# SCH_praktikum-gib-mir-mal-ne-wago.net
KiCad netlist of a schematic drawn in EasyEDA
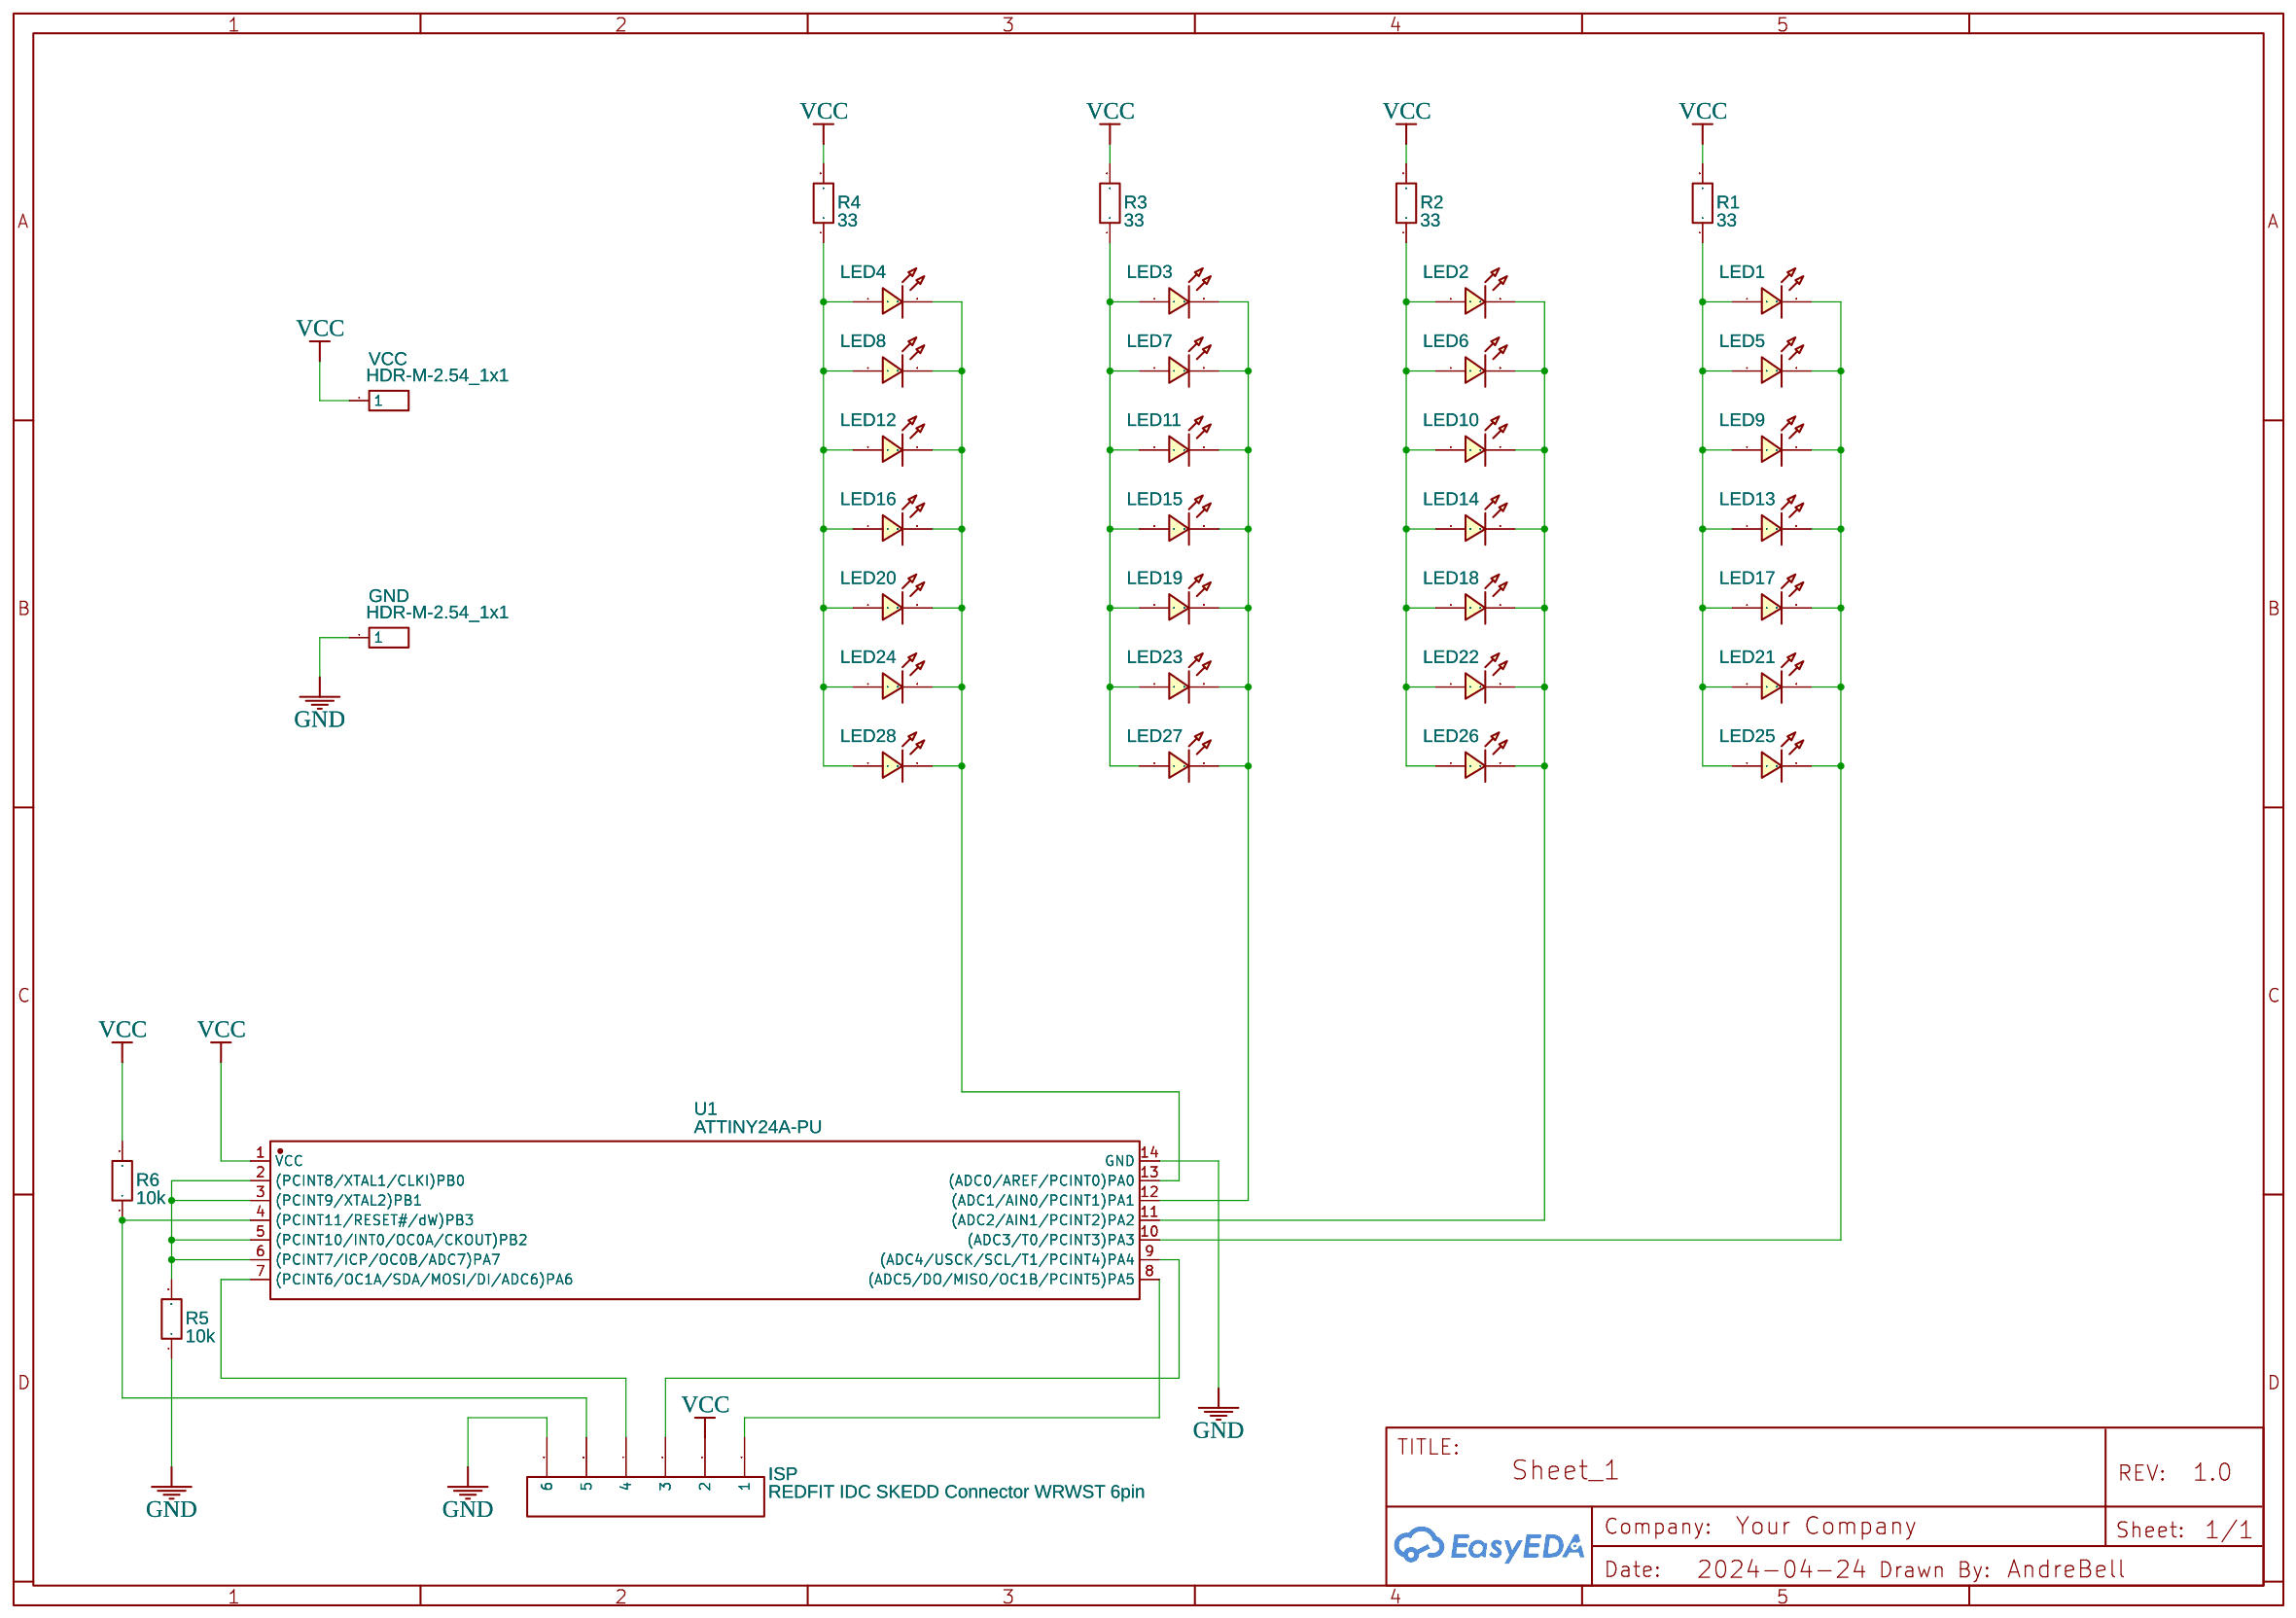
[diagram p0: schematic sheet]

(export (version "E")
  (design (tool "Eeschema 10.0.6"))
  (components
    (comp (ref "GND") (value "HDR-M-2.54_1x1") (libsource (lib "") (part "HDR-M-2.54_1x1")))
    (comp (ref "ISP")
      (value "REDFIT IDC SKEDD Connector WRWST 6pin")
      (libsource (lib "") (part "REDFIT IDC SKEDD Connector WRWST 6pin"))
    )
    (comp (ref "LED1")
      (value "LED-TH-3mm_G")
      (fields
        (field (name "Manufacturer Part") "204-10SYGD/S530-E3")
        (field (name "Manufacturer") "EVERLIGHT(台湾亿光)")
      )
      (libsource (lib "") (part "LED-TH-3mm_G"))
    )
    (comp (ref "LED2")
      (value "LED-TH-3mm_G")
      (fields
        (field (name "Manufacturer Part") "204-10SYGD/S530-E3")
        (field (name "Manufacturer") "EVERLIGHT(台湾亿光)")
      )
      (libsource (lib "") (part "LED-TH-3mm_G"))
    )
    (comp (ref "LED3")
      (value "LED-TH-3mm_G")
      (fields
        (field (name "Manufacturer Part") "204-10SYGD/S530-E3")
        (field (name "Manufacturer") "EVERLIGHT(台湾亿光)")
      )
      (libsource (lib "") (part "LED-TH-3mm_G"))
    )
    (comp (ref "LED4")
      (value "LED-TH-3mm_G")
      (fields
        (field (name "Manufacturer Part") "204-10SYGD/S530-E3")
        (field (name "Manufacturer") "EVERLIGHT(台湾亿光)")
      )
      (libsource (lib "") (part "LED-TH-3mm_G"))
    )
    (comp (ref "LED5")
      (value "LED-TH-3mm_G")
      (fields
        (field (name "Manufacturer Part") "204-10SYGD/S530-E3")
        (field (name "Manufacturer") "EVERLIGHT(台湾亿光)")
      )
      (libsource (lib "") (part "LED-TH-3mm_G"))
    )
    (comp (ref "LED6")
      (value "LED-TH-3mm_G")
      (fields
        (field (name "Manufacturer Part") "204-10SYGD/S530-E3")
        (field (name "Manufacturer") "EVERLIGHT(台湾亿光)")
      )
      (libsource (lib "") (part "LED-TH-3mm_G"))
    )
    (comp (ref "LED7")
      (value "LED-TH-3mm_G")
      (fields
        (field (name "Manufacturer Part") "204-10SYGD/S530-E3")
        (field (name "Manufacturer") "EVERLIGHT(台湾亿光)")
      )
      (libsource (lib "") (part "LED-TH-3mm_G"))
    )
    (comp (ref "LED8")
      (value "LED-TH-3mm_G")
      (fields
        (field (name "Manufacturer Part") "204-10SYGD/S530-E3")
        (field (name "Manufacturer") "EVERLIGHT(台湾亿光)")
      )
      (libsource (lib "") (part "LED-TH-3mm_G"))
    )
    (comp (ref "LED9")
      (value "LED-TH-3mm_G")
      (fields
        (field (name "Manufacturer Part") "204-10SYGD/S530-E3")
        (field (name "Manufacturer") "EVERLIGHT(台湾亿光)")
      )
      (libsource (lib "") (part "LED-TH-3mm_G"))
    )
    (comp (ref "LED10")
      (value "LED-TH-3mm_G")
      (fields
        (field (name "Manufacturer Part") "204-10SYGD/S530-E3")
        (field (name "Manufacturer") "EVERLIGHT(台湾亿光)")
      )
      (libsource (lib "") (part "LED-TH-3mm_G"))
    )
    (comp (ref "LED11")
      (value "LED-TH-3mm_G")
      (fields
        (field (name "Manufacturer Part") "204-10SYGD/S530-E3")
        (field (name "Manufacturer") "EVERLIGHT(台湾亿光)")
      )
      (libsource (lib "") (part "LED-TH-3mm_G"))
    )
    (comp (ref "LED12")
      (value "LED-TH-3mm_G")
      (fields
        (field (name "Manufacturer Part") "204-10SYGD/S530-E3")
        (field (name "Manufacturer") "EVERLIGHT(台湾亿光)")
      )
      (libsource (lib "") (part "LED-TH-3mm_G"))
    )
    (comp (ref "LED13")
      (value "LED-TH-3mm_G")
      (fields
        (field (name "Manufacturer Part") "204-10SYGD/S530-E3")
        (field (name "Manufacturer") "EVERLIGHT(台湾亿光)")
      )
      (libsource (lib "") (part "LED-TH-3mm_G"))
    )
    (comp (ref "LED14")
      (value "LED-TH-3mm_G")
      (fields
        (field (name "Manufacturer Part") "204-10SYGD/S530-E3")
        (field (name "Manufacturer") "EVERLIGHT(台湾亿光)")
      )
      (libsource (lib "") (part "LED-TH-3mm_G"))
    )
    (comp (ref "LED15")
      (value "LED-TH-3mm_G")
      (fields
        (field (name "Manufacturer Part") "204-10SYGD/S530-E3")
        (field (name "Manufacturer") "EVERLIGHT(台湾亿光)")
      )
      (libsource (lib "") (part "LED-TH-3mm_G"))
    )
    (comp (ref "LED16")
      (value "LED-TH-3mm_G")
      (fields
        (field (name "Manufacturer Part") "204-10SYGD/S530-E3")
        (field (name "Manufacturer") "EVERLIGHT(台湾亿光)")
      )
      (libsource (lib "") (part "LED-TH-3mm_G"))
    )
    (comp (ref "LED17")
      (value "LED-TH-3mm_G")
      (fields
        (field (name "Manufacturer Part") "204-10SYGD/S530-E3")
        (field (name "Manufacturer") "EVERLIGHT(台湾亿光)")
      )
      (libsource (lib "") (part "LED-TH-3mm_G"))
    )
    (comp (ref "LED18")
      (value "LED-TH-3mm_G")
      (fields
        (field (name "Manufacturer Part") "204-10SYGD/S530-E3")
        (field (name "Manufacturer") "EVERLIGHT(台湾亿光)")
      )
      (libsource (lib "") (part "LED-TH-3mm_G"))
    )
    (comp (ref "LED19")
      (value "LED-TH-3mm_G")
      (fields
        (field (name "Manufacturer Part") "204-10SYGD/S530-E3")
        (field (name "Manufacturer") "EVERLIGHT(台湾亿光)")
      )
      (libsource (lib "") (part "LED-TH-3mm_G"))
    )
    (comp (ref "LED20")
      (value "LED-TH-3mm_G")
      (fields
        (field (name "Manufacturer Part") "204-10SYGD/S530-E3")
        (field (name "Manufacturer") "EVERLIGHT(台湾亿光)")
      )
      (libsource (lib "") (part "LED-TH-3mm_G"))
    )
    (comp (ref "LED21")
      (value "LED-TH-3mm_G")
      (fields
        (field (name "Manufacturer Part") "204-10SYGD/S530-E3")
        (field (name "Manufacturer") "EVERLIGHT(台湾亿光)")
      )
      (libsource (lib "") (part "LED-TH-3mm_G"))
    )
    (comp (ref "LED22")
      (value "LED-TH-3mm_G")
      (fields
        (field (name "Manufacturer Part") "204-10SYGD/S530-E3")
        (field (name "Manufacturer") "EVERLIGHT(台湾亿光)")
      )
      (libsource (lib "") (part "LED-TH-3mm_G"))
    )
    (comp (ref "LED23")
      (value "LED-TH-3mm_G")
      (fields
        (field (name "Manufacturer Part") "204-10SYGD/S530-E3")
        (field (name "Manufacturer") "EVERLIGHT(台湾亿光)")
      )
      (libsource (lib "") (part "LED-TH-3mm_G"))
    )
    (comp (ref "LED24")
      (value "LED-TH-3mm_G")
      (fields
        (field (name "Manufacturer Part") "204-10SYGD/S530-E3")
        (field (name "Manufacturer") "EVERLIGHT(台湾亿光)")
      )
      (libsource (lib "") (part "LED-TH-3mm_G"))
    )
    (comp (ref "LED25")
      (value "LED-TH-3mm_G")
      (fields
        (field (name "Manufacturer Part") "204-10SYGD/S530-E3")
        (field (name "Manufacturer") "EVERLIGHT(台湾亿光)")
      )
      (libsource (lib "") (part "LED-TH-3mm_G"))
    )
    (comp (ref "LED26")
      (value "LED-TH-3mm_G")
      (fields
        (field (name "Manufacturer Part") "204-10SYGD/S530-E3")
        (field (name "Manufacturer") "EVERLIGHT(台湾亿光)")
      )
      (libsource (lib "") (part "LED-TH-3mm_G"))
    )
    (comp (ref "LED27")
      (value "LED-TH-3mm_G")
      (fields
        (field (name "Manufacturer Part") "204-10SYGD/S530-E3")
        (field (name "Manufacturer") "EVERLIGHT(台湾亿光)")
      )
      (libsource (lib "") (part "LED-TH-3mm_G"))
    )
    (comp (ref "LED28")
      (value "LED-TH-3mm_G")
      (fields
        (field (name "Manufacturer Part") "204-10SYGD/S530-E3")
        (field (name "Manufacturer") "EVERLIGHT(台湾亿光)")
      )
      (libsource (lib "") (part "LED-TH-3mm_G"))
    )
    (comp (ref "R1") (value "33") (libsource (lib "") (part "R_AXIAL-0.3_EU")))
    (comp (ref "R2") (value "33") (libsource (lib "") (part "R_AXIAL-0.3_EU")))
    (comp (ref "R3") (value "33") (libsource (lib "") (part "R_AXIAL-0.3_EU")))
    (comp (ref "R4") (value "33") (libsource (lib "") (part "R_AXIAL-0.3_EU")))
    (comp (ref "R5") (value "10k") (libsource (lib "") (part "R_AXIAL-0.3_EU")))
    (comp (ref "R6") (value "10k") (libsource (lib "") (part "R_AXIAL-0.3_EU")))
    (comp (ref "U1")
      (value "ATTINY24A-PU")
      (fields (field (name "Manufacturer") "MICROCHIP(美国微芯)"))
      (libsource (lib "") (part "ATTINY24A-PU"))
    )
    (comp (ref "VCC") (value "HDR-M-2.54_1x1") (libsource (lib "") (part "HDR-M-2.54_1x1_1")))
  )
  (nets
    (net (code "1") (name "GND") (class "Default")
      (node (ref "GND") (pin "1") (pinfunction "1_1") (pintype "input"))
      (node (ref "ISP") (pin "6") (pinfunction "6_6") (pintype "unspecified"))
      (node (ref "R5") (pin "1") (pinfunction "1_1") (pintype "unspecified"))
      (node (ref "U1") (pin "14") (pinfunction "GND_14") (pintype "unspecified"))
    )
    (net (code "2") (name "Net-(LED1-Pad1)") (class "Default")
      (node (ref "LED1") (pin "1") (pinfunction "1_1") (pintype "unspecified"))
      (node (ref "LED13") (pin "1") (pinfunction "1_1") (pintype "unspecified"))
      (node (ref "LED17") (pin "1") (pinfunction "1_1") (pintype "unspecified"))
      (node (ref "LED21") (pin "1") (pinfunction "1_1") (pintype "unspecified"))
      (node (ref "LED25") (pin "1") (pinfunction "1_1") (pintype "unspecified"))
      (node (ref "LED5") (pin "1") (pinfunction "1_1") (pintype "unspecified"))
      (node (ref "LED9") (pin "1") (pinfunction "1_1") (pintype "unspecified"))
      (node (ref "R1") (pin "1") (pinfunction "1_1") (pintype "unspecified"))
    )
    (net (code "3") (name "Net-(LED10-Pad1)") (class "Default")
      (node (ref "LED10") (pin "1") (pinfunction "1_1") (pintype "unspecified"))
      (node (ref "LED14") (pin "1") (pinfunction "1_1") (pintype "unspecified"))
      (node (ref "LED18") (pin "1") (pinfunction "1_1") (pintype "unspecified"))
      (node (ref "LED2") (pin "1") (pinfunction "1_1") (pintype "unspecified"))
      (node (ref "LED22") (pin "1") (pinfunction "1_1") (pintype "unspecified"))
      (node (ref "LED26") (pin "1") (pinfunction "1_1") (pintype "unspecified"))
      (node (ref "LED6") (pin "1") (pinfunction "1_1") (pintype "unspecified"))
      (node (ref "R2") (pin "1") (pinfunction "1_1") (pintype "unspecified"))
    )
    (net (code "4") (name "Net-(LED11-Pad1)") (class "Default")
      (node (ref "LED11") (pin "1") (pinfunction "1_1") (pintype "unspecified"))
      (node (ref "LED15") (pin "1") (pinfunction "1_1") (pintype "unspecified"))
      (node (ref "LED19") (pin "1") (pinfunction "1_1") (pintype "unspecified"))
      (node (ref "LED23") (pin "1") (pinfunction "1_1") (pintype "unspecified"))
      (node (ref "LED27") (pin "1") (pinfunction "1_1") (pintype "unspecified"))
      (node (ref "LED3") (pin "1") (pinfunction "1_1") (pintype "unspecified"))
      (node (ref "LED7") (pin "1") (pinfunction "1_1") (pintype "unspecified"))
      (node (ref "R3") (pin "1") (pinfunction "1_1") (pintype "unspecified"))
    )
    (net (code "5") (name "Net-(LED12-Pad1)") (class "Default")
      (node (ref "LED12") (pin "1") (pinfunction "1_1") (pintype "unspecified"))
      (node (ref "LED16") (pin "1") (pinfunction "1_1") (pintype "unspecified"))
      (node (ref "LED20") (pin "1") (pinfunction "1_1") (pintype "unspecified"))
      (node (ref "LED24") (pin "1") (pinfunction "1_1") (pintype "unspecified"))
      (node (ref "LED28") (pin "1") (pinfunction "1_1") (pintype "unspecified"))
      (node (ref "LED4") (pin "1") (pinfunction "1_1") (pintype "unspecified"))
      (node (ref "LED8") (pin "1") (pinfunction "1_1") (pintype "unspecified"))
      (node (ref "R4") (pin "1") (pinfunction "1_1") (pintype "unspecified"))
    )
    (net (code "6") (name "Net-(U1-(ADC0{slash}AREF{slash}PCINT0)PA0)") (class "Default")
      (node (ref "LED12") (pin "2") (pinfunction "2_2") (pintype "unspecified"))
      (node (ref "LED16") (pin "2") (pinfunction "2_2") (pintype "unspecified"))
      (node (ref "LED20") (pin "2") (pinfunction "2_2") (pintype "unspecified"))
      (node (ref "LED24") (pin "2") (pinfunction "2_2") (pintype "unspecified"))
      (node (ref "LED28") (pin "2") (pinfunction "2_2") (pintype "unspecified"))
      (node (ref "LED4") (pin "2") (pinfunction "2_2") (pintype "unspecified"))
      (node (ref "LED8") (pin "2") (pinfunction "2_2") (pintype "unspecified"))
      (node (ref "U1") (pin "13") (pinfunction "(ADC0/AREF/PCINT0)PA0_13") (pintype "unspecified"))
    )
    (net (code "7") (name "Net-(U1-(ADC1{slash}AIN0{slash}PCINT1)PA1)") (class "Default")
      (node (ref "LED11") (pin "2") (pinfunction "2_2") (pintype "unspecified"))
      (node (ref "LED15") (pin "2") (pinfunction "2_2") (pintype "unspecified"))
      (node (ref "LED19") (pin "2") (pinfunction "2_2") (pintype "unspecified"))
      (node (ref "LED23") (pin "2") (pinfunction "2_2") (pintype "unspecified"))
      (node (ref "LED27") (pin "2") (pinfunction "2_2") (pintype "unspecified"))
      (node (ref "LED3") (pin "2") (pinfunction "2_2") (pintype "unspecified"))
      (node (ref "LED7") (pin "2") (pinfunction "2_2") (pintype "unspecified"))
      (node (ref "U1") (pin "12") (pinfunction "(ADC1/AIN0/PCINT1)PA1_12") (pintype "unspecified"))
    )
    (net (code "8") (name "Net-(U1-(ADC2{slash}AIN1{slash}PCINT2)PA2)") (class "Default")
      (node (ref "LED10") (pin "2") (pinfunction "2_2") (pintype "unspecified"))
      (node (ref "LED14") (pin "2") (pinfunction "2_2") (pintype "unspecified"))
      (node (ref "LED18") (pin "2") (pinfunction "2_2") (pintype "unspecified"))
      (node (ref "LED2") (pin "2") (pinfunction "2_2") (pintype "unspecified"))
      (node (ref "LED22") (pin "2") (pinfunction "2_2") (pintype "unspecified"))
      (node (ref "LED26") (pin "2") (pinfunction "2_2") (pintype "unspecified"))
      (node (ref "LED6") (pin "2") (pinfunction "2_2") (pintype "unspecified"))
      (node (ref "U1") (pin "11") (pinfunction "(ADC2/AIN1/PCINT2)PA2_11") (pintype "unspecified"))
    )
    (net (code "9") (name "Net-(U1-(ADC3{slash}T0{slash}PCINT3)PA3)") (class "Default")
      (node (ref "LED1") (pin "2") (pinfunction "2_2") (pintype "unspecified"))
      (node (ref "LED13") (pin "2") (pinfunction "2_2") (pintype "unspecified"))
      (node (ref "LED17") (pin "2") (pinfunction "2_2") (pintype "unspecified"))
      (node (ref "LED21") (pin "2") (pinfunction "2_2") (pintype "unspecified"))
      (node (ref "LED25") (pin "2") (pinfunction "2_2") (pintype "unspecified"))
      (node (ref "LED5") (pin "2") (pinfunction "2_2") (pintype "unspecified"))
      (node (ref "LED9") (pin "2") (pinfunction "2_2") (pintype "unspecified"))
      (node (ref "U1") (pin "10") (pinfunction "(ADC3/T0/PCINT3)PA3_10") (pintype "unspecified"))
    )
    (net (code "10") (name "Net-(U1-(ADC4{slash}USCK{slash}SCL{slash}T1{slash}PCINT4)PA4)") (class "Default")
      (node (ref "ISP") (pin "3") (pinfunction "3_3") (pintype "unspecified"))
      (node (ref "U1") (pin "9") (pinfunction "(ADC4/USCK/SCL/T1/PCINT4)PA4_9") (pintype "unspecified"))
    )
    (net (code "11") (name "Net-(U1-(ADC5{slash}DO{slash}MISO{slash}OC1B{slash}PCINT5)PA5)") (class "Default")
      (node (ref "ISP") (pin "1") (pinfunction "1_1") (pintype "unspecified"))
      (node (ref "U1") (pin "8") (pinfunction "(ADC5/DO/MISO/OC1B/PCINT5)PA5_8") (pintype "unspecified"))
    )
    (net (code "12") (name "Net-(U1-(PCINT6{slash}OC1A{slash}SDA{slash}MOSI{slash}DI{slash}ADC6)PA6)") (class "Default")
      (node (ref "ISP") (pin "4") (pinfunction "4_4") (pintype "unspecified"))
      (node (ref "U1") (pin "7") (pinfunction "(PCINT6/OC1A/SDA/MOSI/DI/ADC6)PA6_7") (pintype "unspecified"))
    )
    (net (code "13") (name "Net-(U1-(PCINT10{slash}INT0{slash}OC0A{slash}CKOUT)PB2)") (class "Default")
      (node (ref "R5") (pin "2") (pinfunction "2_2") (pintype "unspecified"))
      (node (ref "U1") (pin "2") (pinfunction "(PCINT8/XTAL1/CLKI)PB0_2") (pintype "unspecified"))
      (node (ref "U1") (pin "3") (pinfunction "(PCINT9/XTAL2)PB1_3") (pintype "unspecified"))
      (node (ref "U1") (pin "5") (pinfunction "(PCINT10/INT0/OC0A/CKOUT)PB2_5") (pintype "unspecified"))
      (node (ref "U1") (pin "6") (pinfunction "(PCINT7/ICP/OC0B/ADC7)PA7_6") (pintype "unspecified"))
    )
    (net (code "14") (name "Net-(U1-(PCINT11{slash}RESET#{slash}dW)PB3)") (class "Default")
      (node (ref "ISP") (pin "5") (pinfunction "5_5") (pintype "unspecified"))
      (node (ref "R6") (pin "1") (pinfunction "1_1") (pintype "unspecified"))
      (node (ref "U1") (pin "4") (pinfunction "(PCINT11/RESET#/dW)PB3_4") (pintype "unspecified"))
    )
    (net (code "15") (name "VCC") (class "Default")
      (node (ref "ISP") (pin "2") (pinfunction "2_2") (pintype "unspecified"))
      (node (ref "R1") (pin "2") (pinfunction "2_2") (pintype "unspecified"))
      (node (ref "R2") (pin "2") (pinfunction "2_2") (pintype "unspecified"))
      (node (ref "R3") (pin "2") (pinfunction "2_2") (pintype "unspecified"))
      (node (ref "R4") (pin "2") (pinfunction "2_2") (pintype "unspecified"))
      (node (ref "R6") (pin "2") (pinfunction "2_2") (pintype "unspecified"))
      (node (ref "U1") (pin "1") (pinfunction "VCC_1") (pintype "unspecified"))
      (node (ref "VCC") (pin "1") (pinfunction "1_1") (pintype "input"))
    )
  )
)
